# KAI_EFUSE_2_0_0.net
KiCad netlist of a schematic drawn in EAGLE
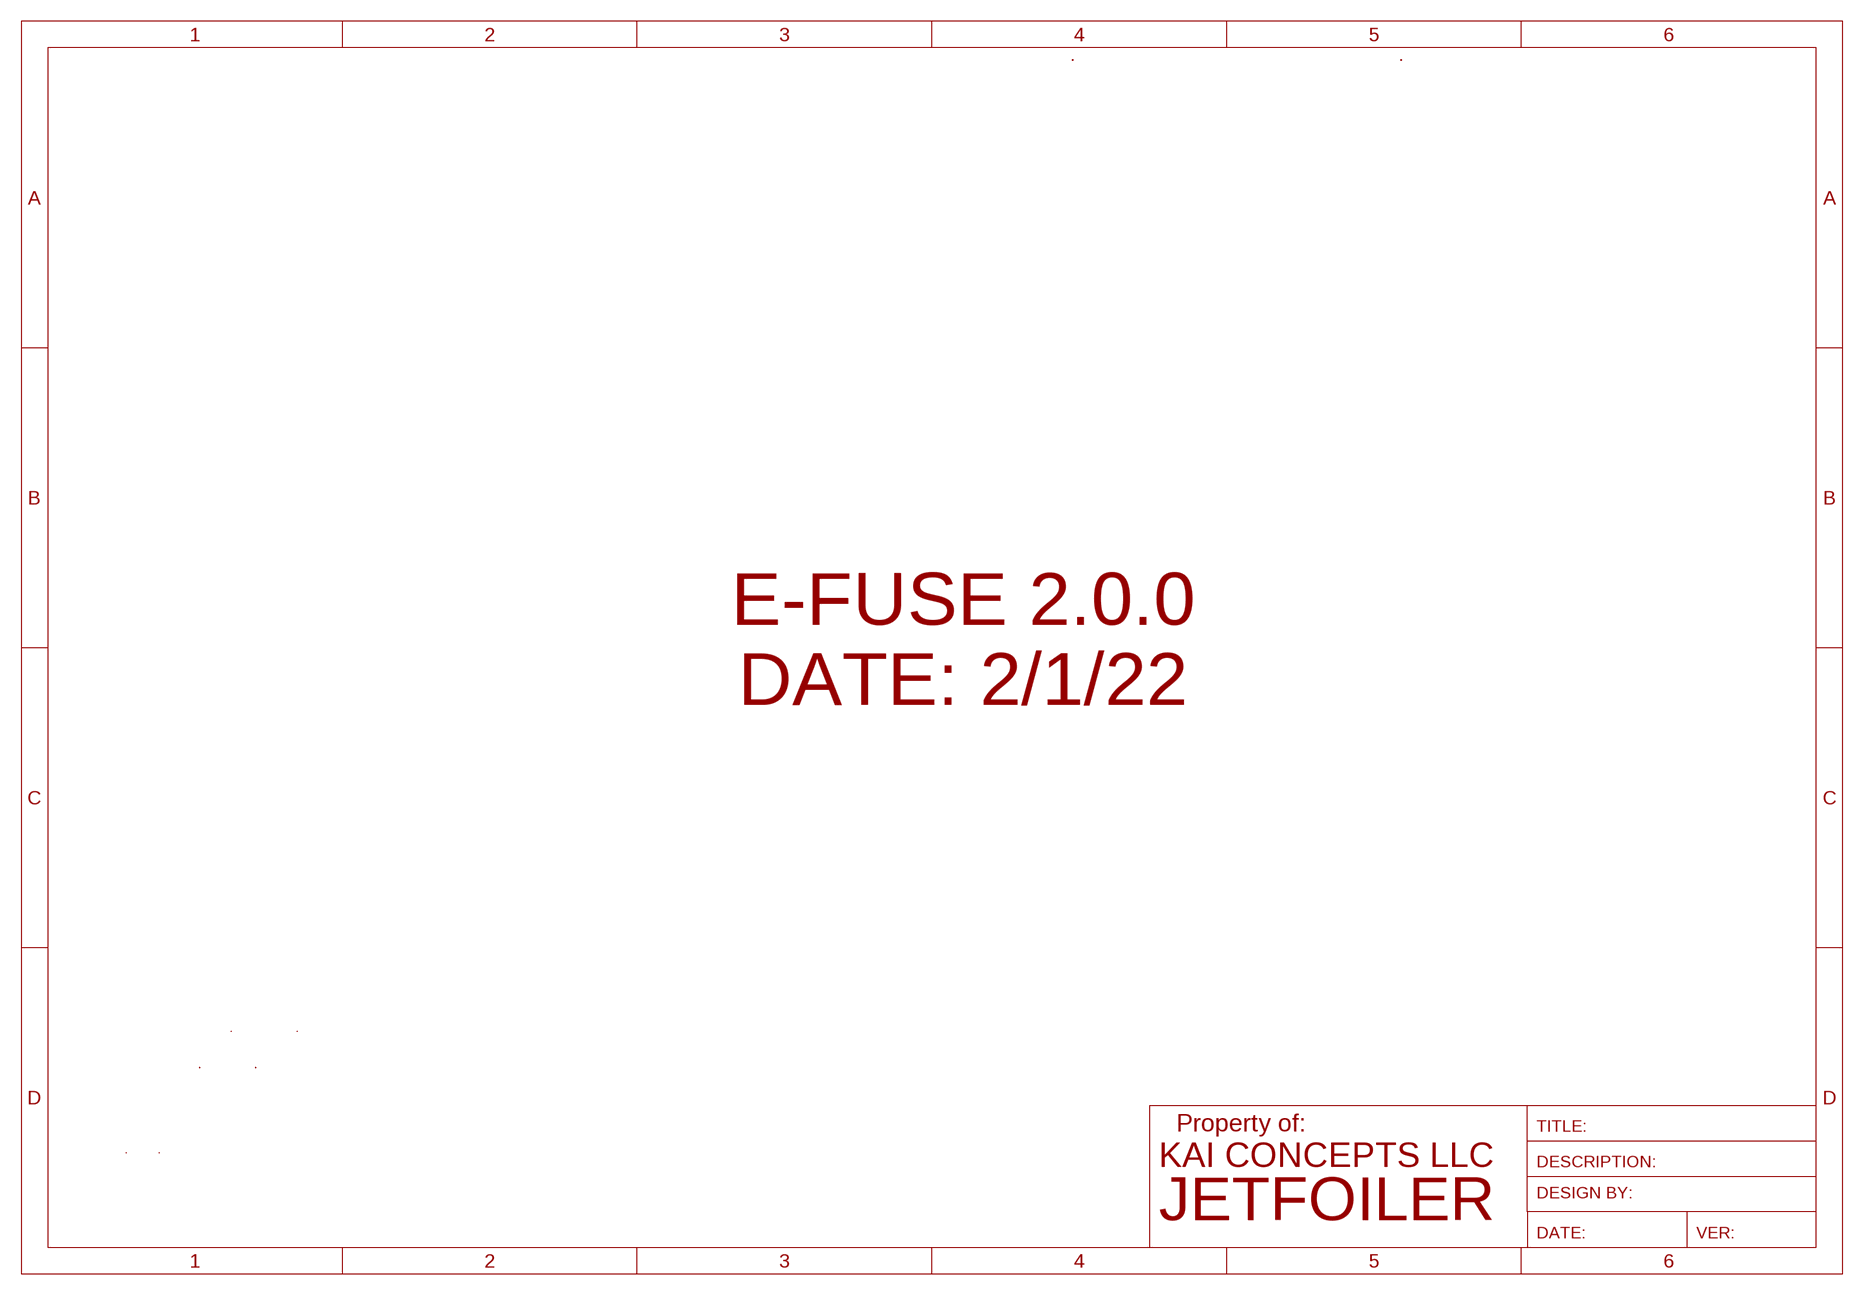
[diagram p0: schematic, sheet 1]
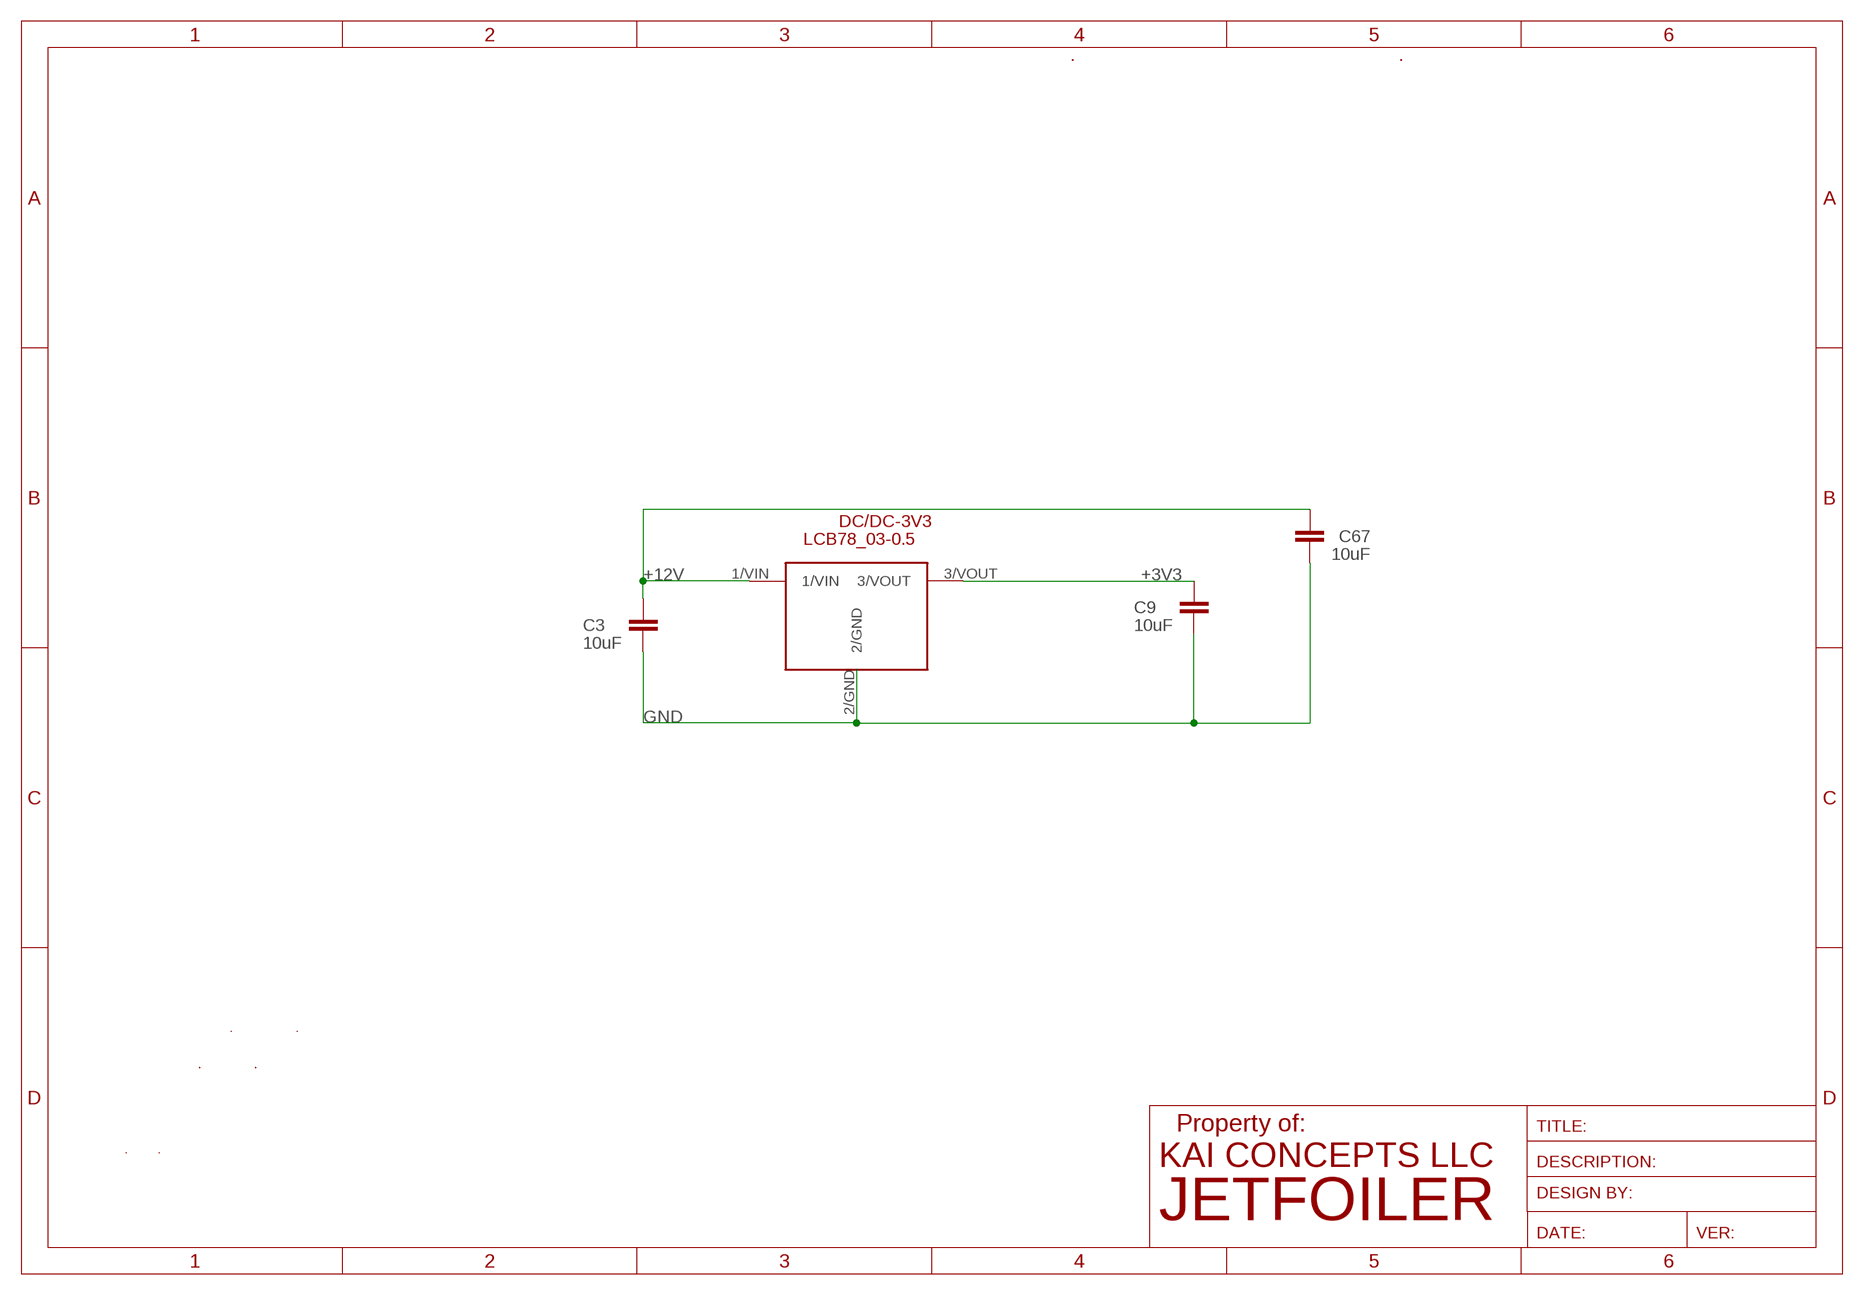
[diagram p1: schematic, sheet 2]
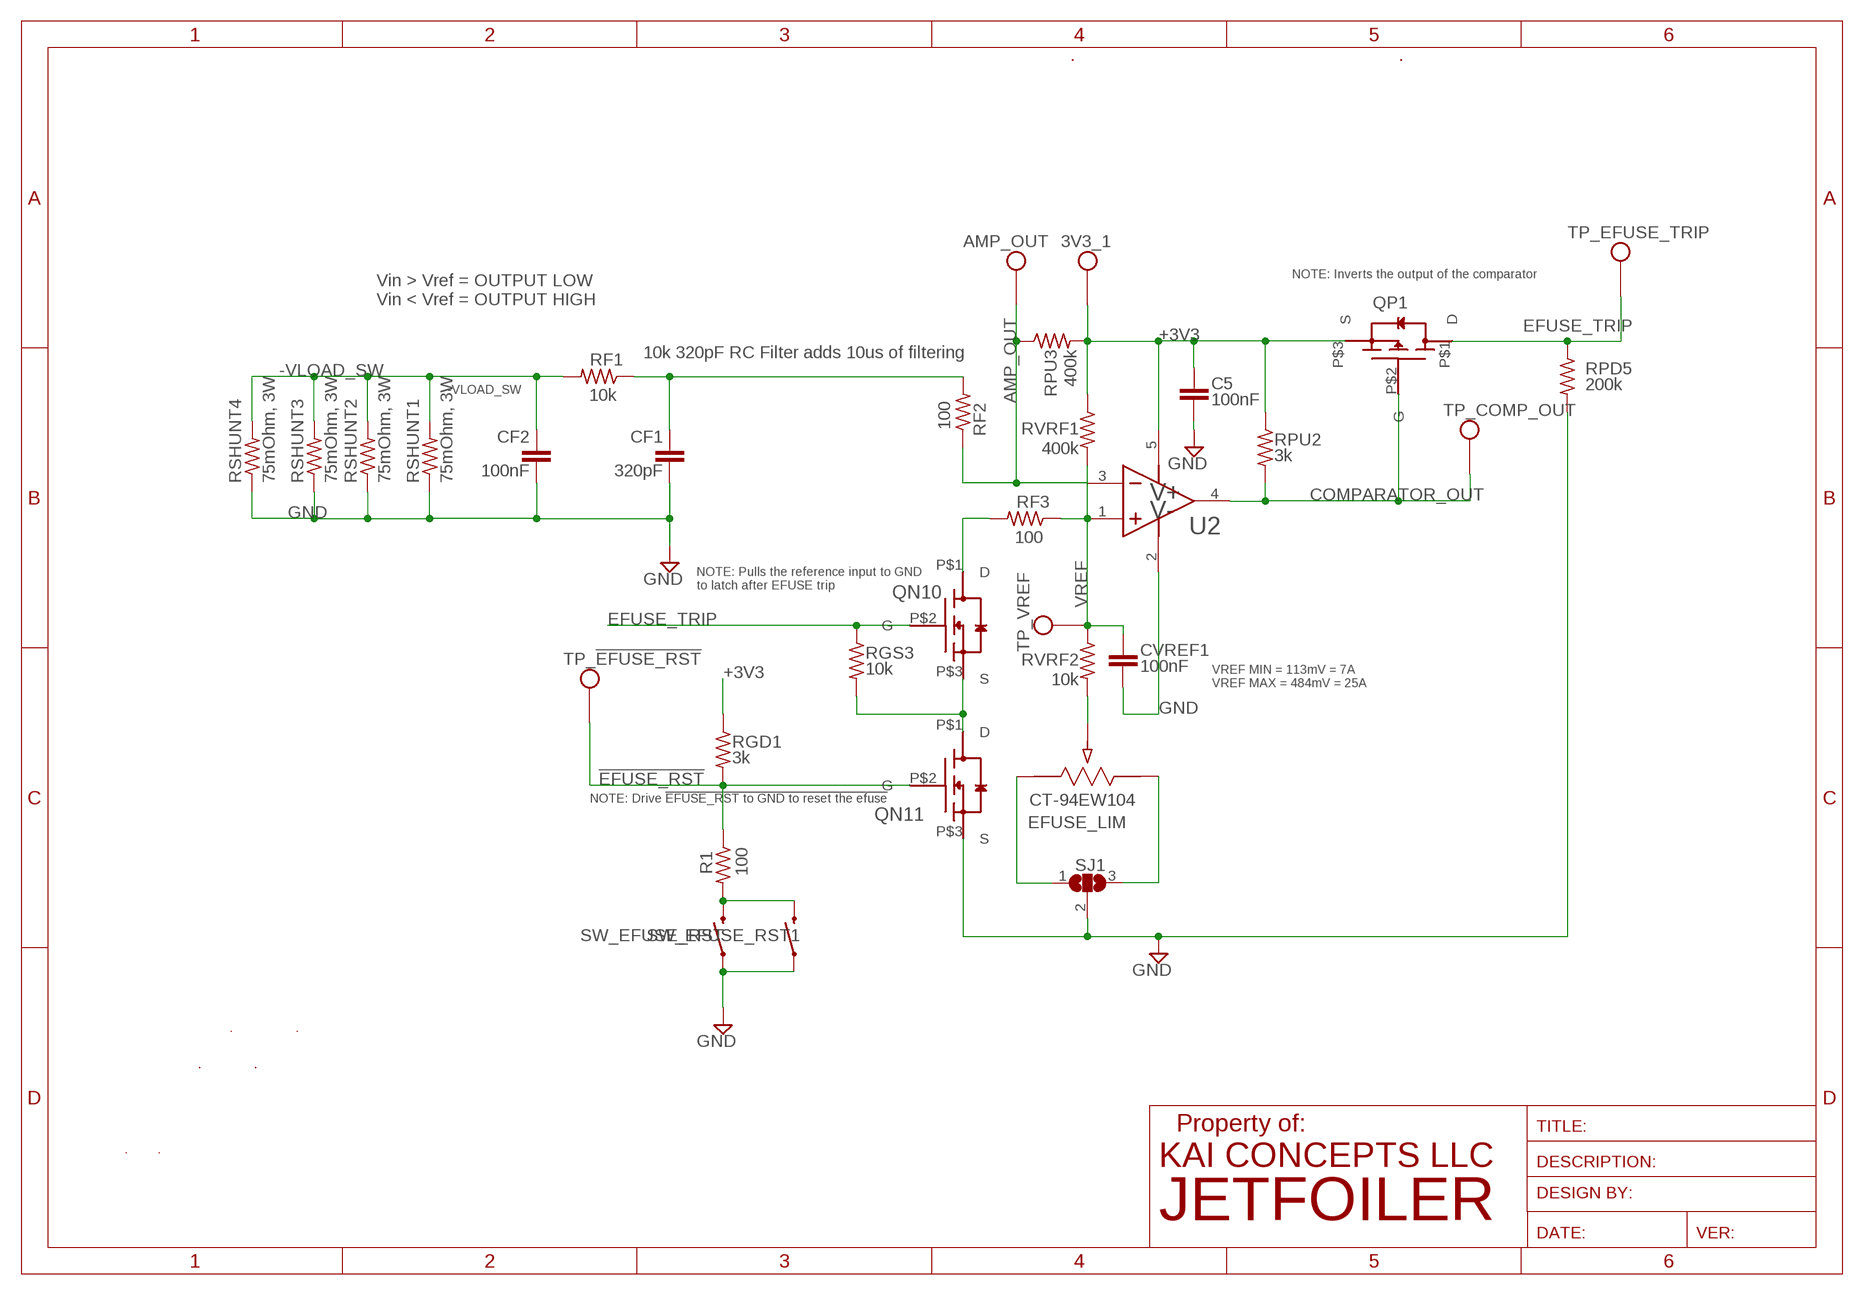
[diagram p2: schematic, sheet 3]
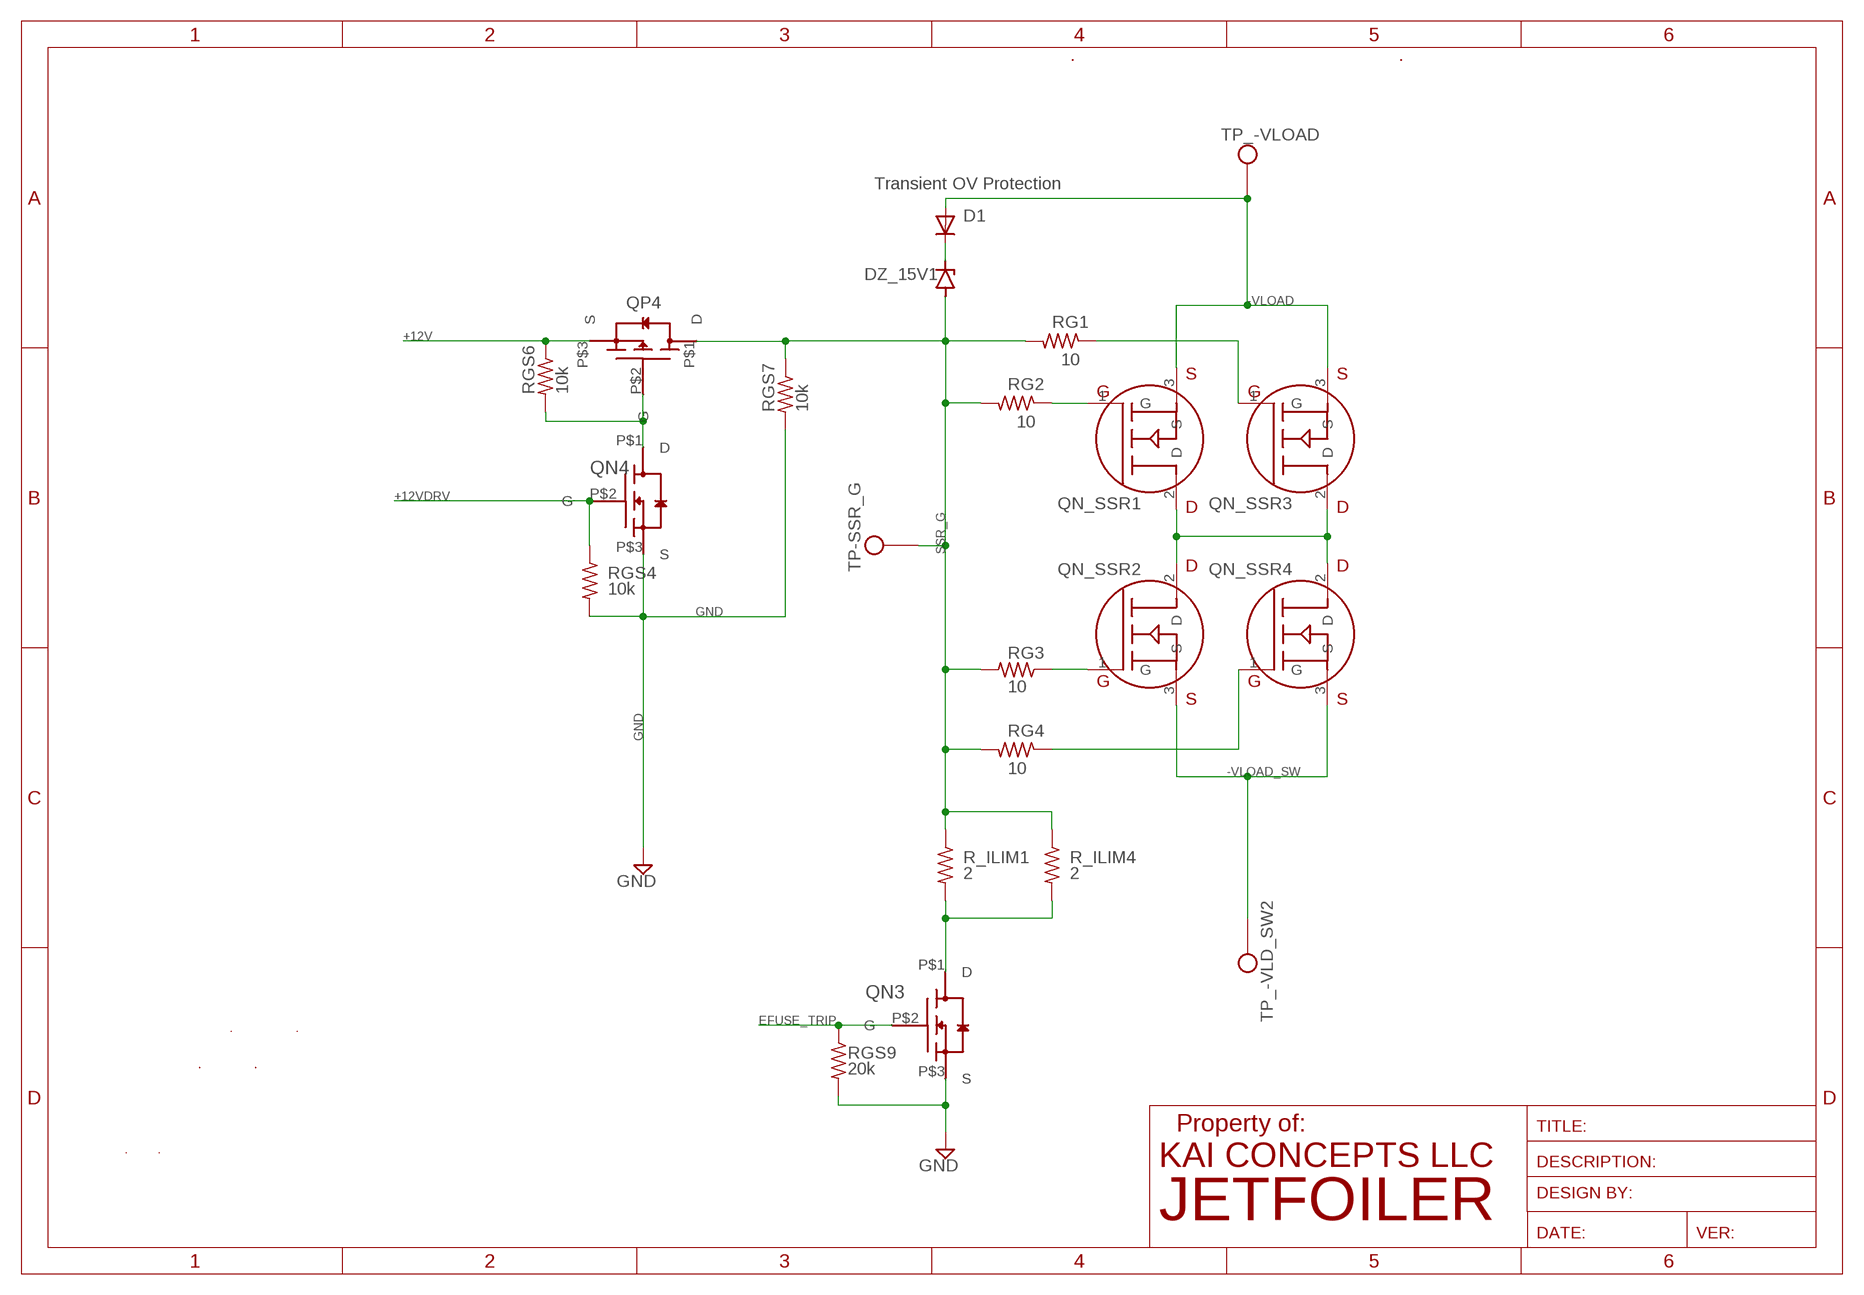
[diagram p3: schematic, sheet 4]
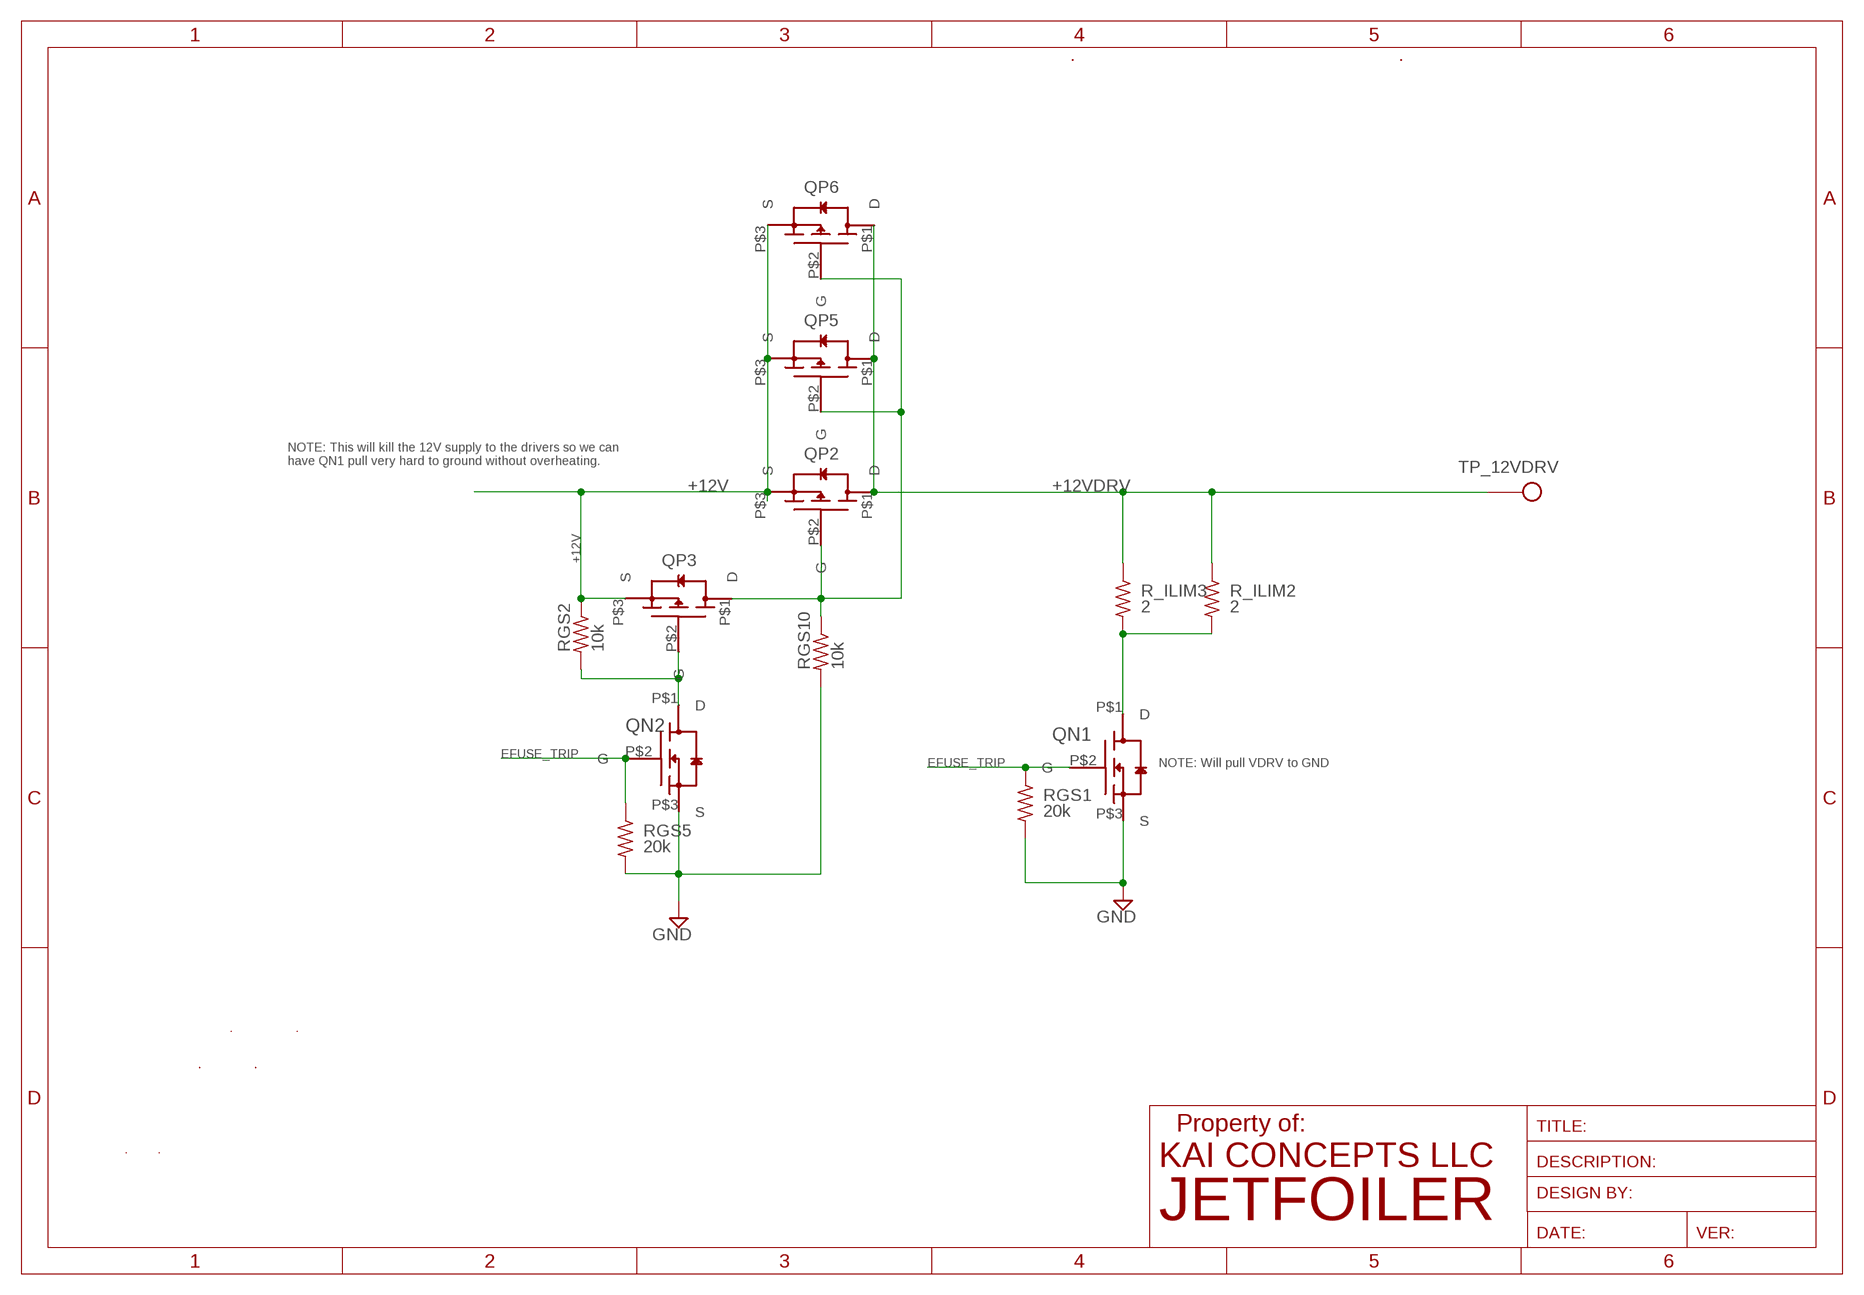
[diagram p4: schematic, sheet 5]
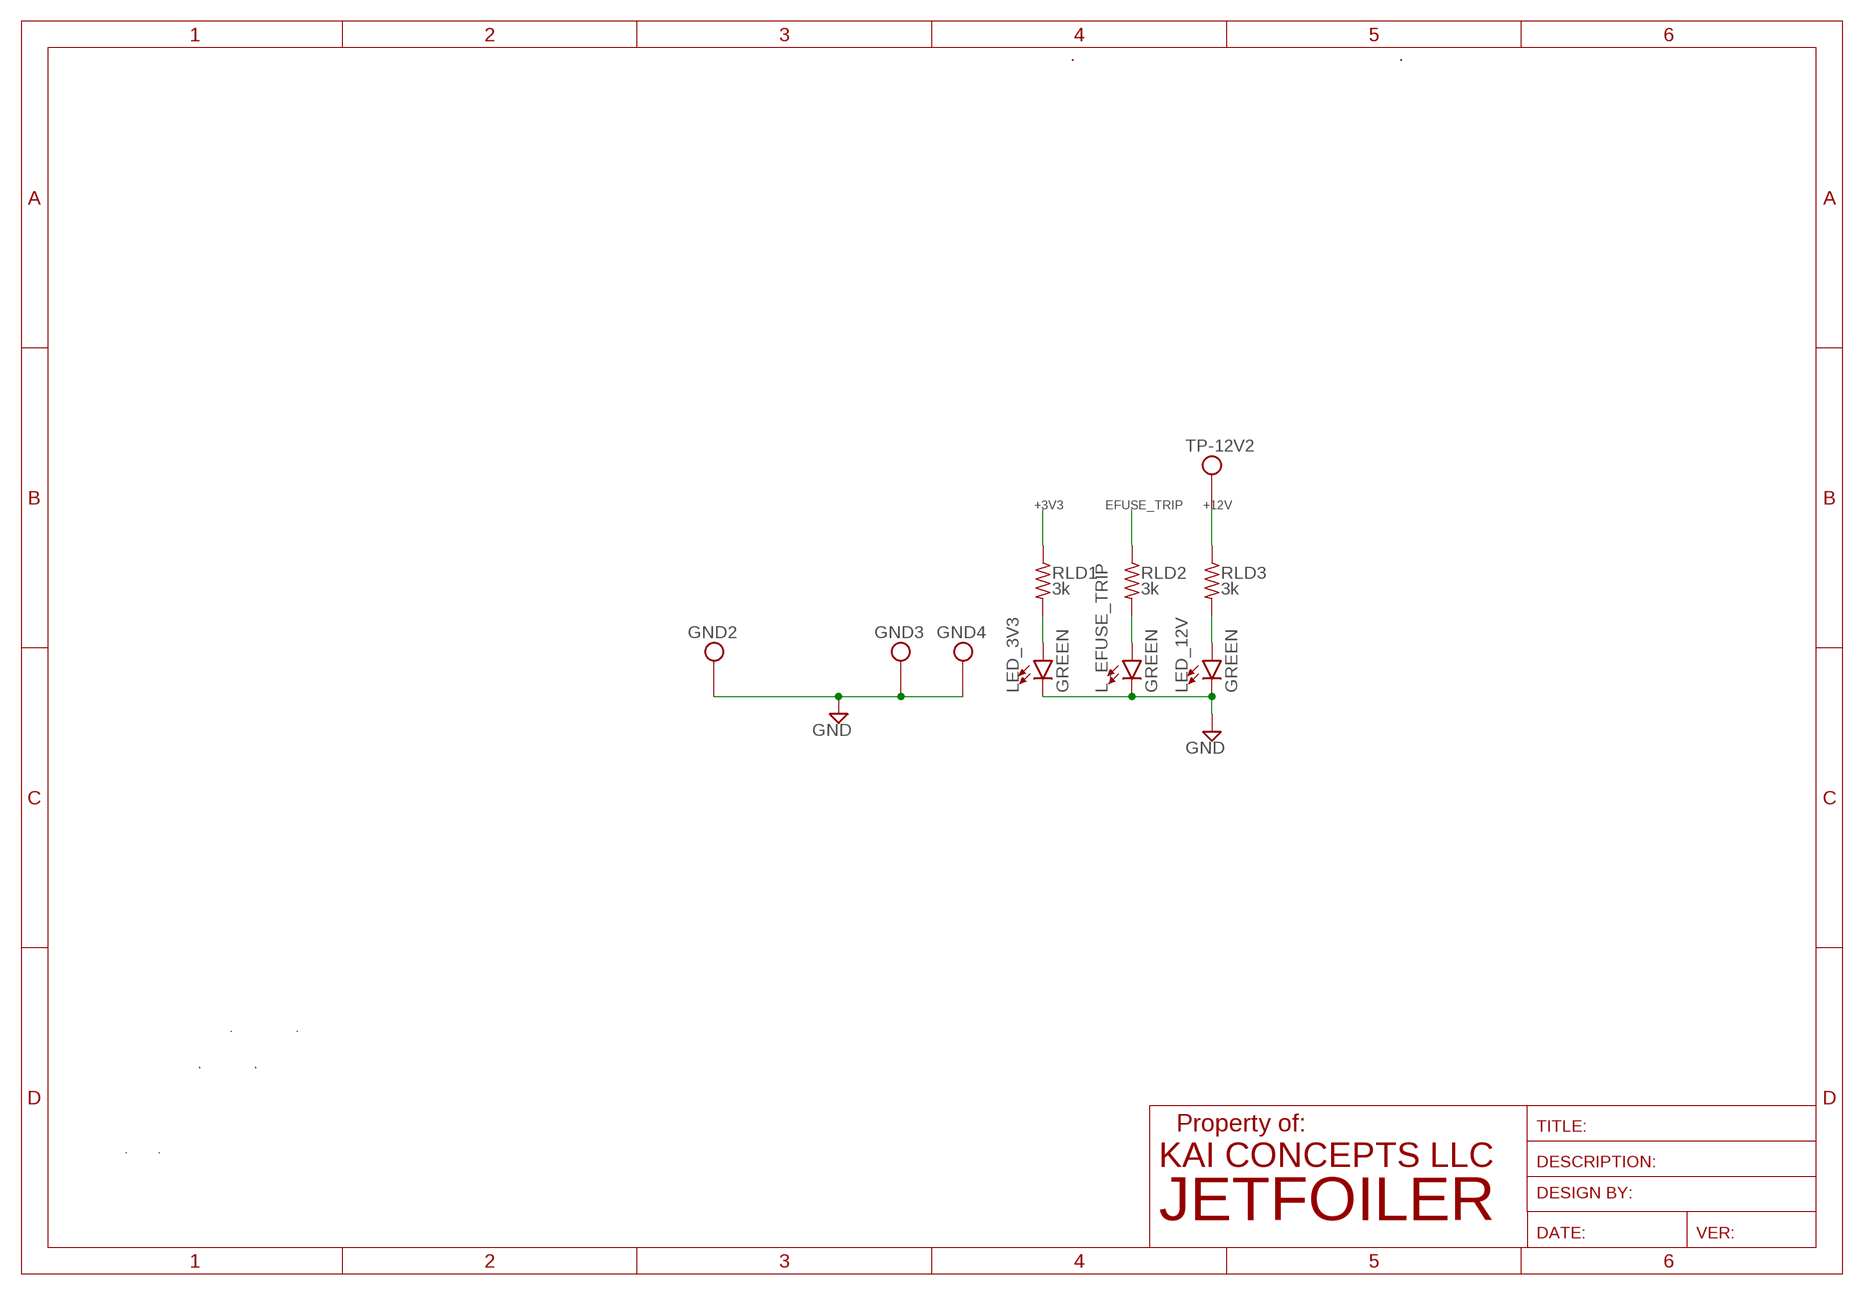
[diagram p5: schematic, sheet 6]
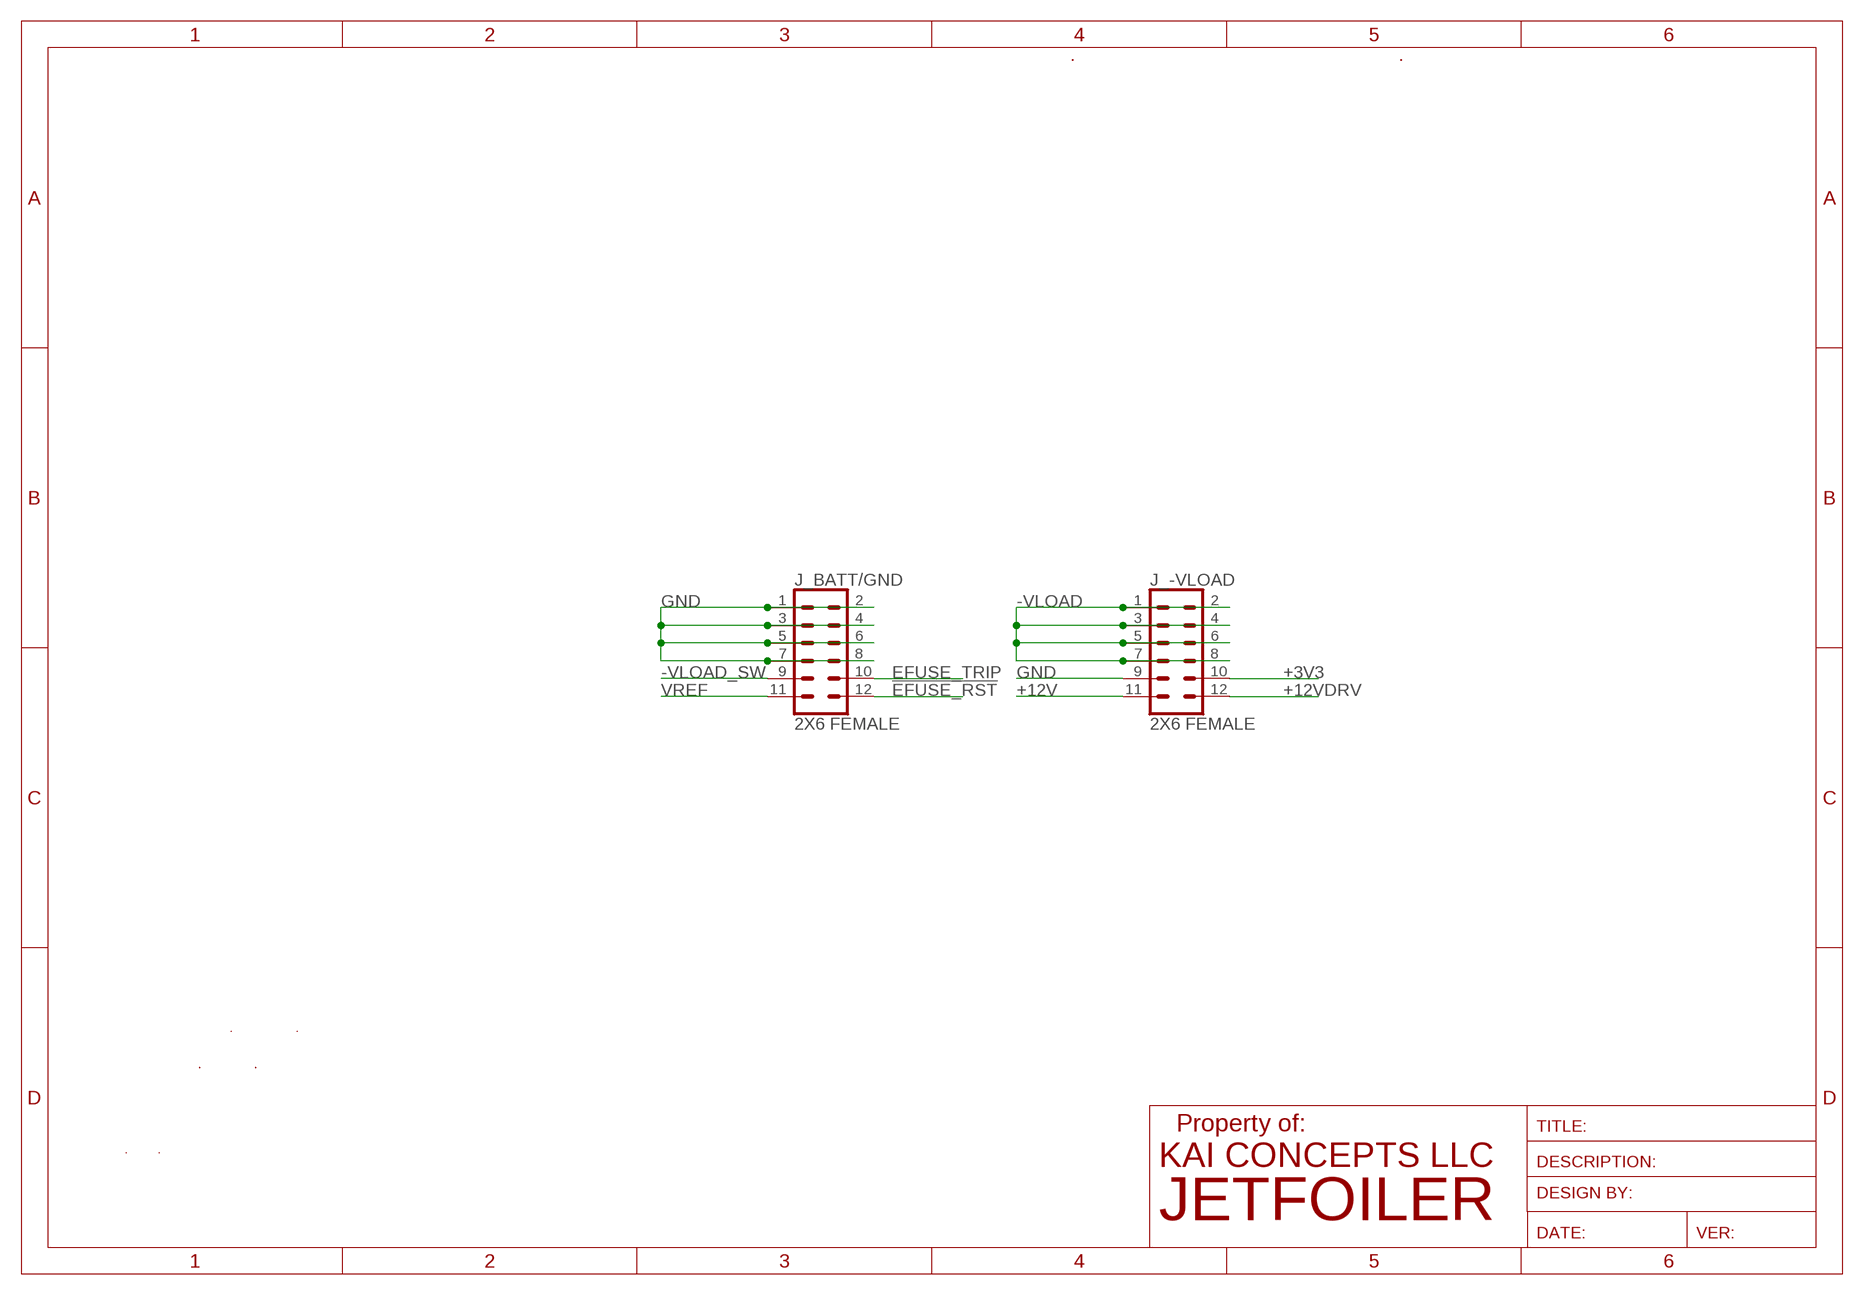
[diagram p6: schematic, sheet 7]
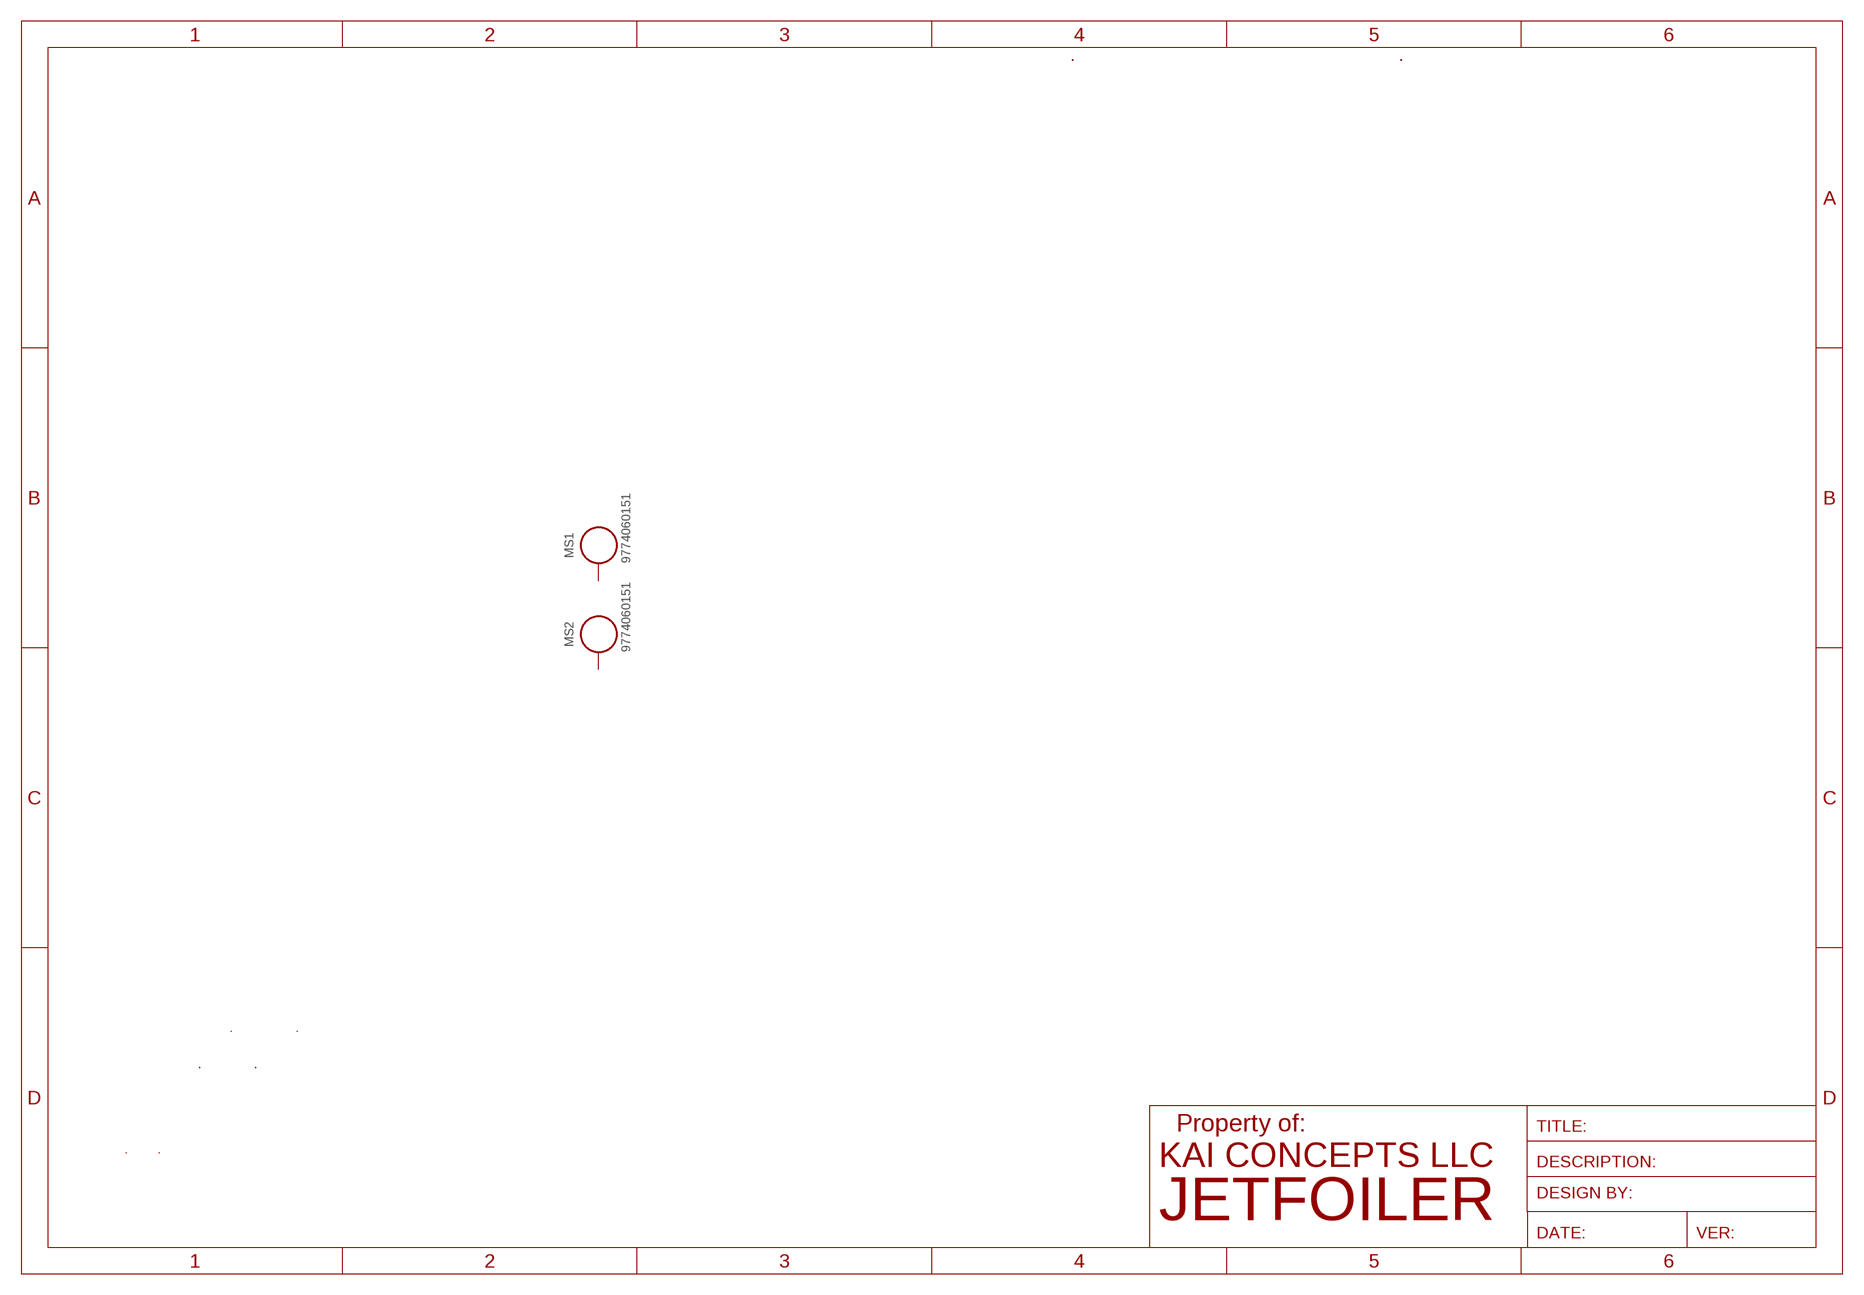
[diagram p7: schematic, sheet 8]

(export (version "E")
  (design (tool "Eeschema 10.0.6"))
  (components
    (comp (ref "QN1")
      (value "NFET-(SOT-23-3)(TO-236-3)(SC-59)")
      (footprint "eagle-import:SOT23,SC-59,TO-236-3")
      (fields (field (name "LCSC_PART") "C296286"))
      (libsource (lib "eagle-import") (part "NFET-(SOT-23-3)(TO-236-3)(SC-59)"))
    )
    (comp (ref "QN2")
      (value "NFET-(SOT-23-3)(TO-236-3)(SC-59)")
      (footprint "eagle-import:SOT23,SC-59,TO-236-3")
      (fields (field (name "LCSC_PART") "C296286"))
      (libsource (lib "eagle-import") (part "NFET-(SOT-23-3)(TO-236-3)(SC-59)"))
    )
    (comp (ref "QP2")
      (value "PFET-(SOT-23-3)(TO-236-3)(SC-59)")
      (footprint "eagle-import:SOT23,SC-59,TO-236-3")
      (fields (field (name "LCSC_PART") "C489594"))
      (libsource (lib "eagle-import") (part "PFET-(SOT-23-3)(TO-236-3)(SC-59)"))
    )
    (comp (ref "QP3")
      (value "PFET-(SOT-23-3)(TO-236-3)(SC-59)")
      (footprint "eagle-import:SOT23,SC-59,TO-236-3")
      (fields (field (name "LCSC_PART") "C489594"))
      (libsource (lib "eagle-import") (part "PFET-(SOT-23-3)(TO-236-3)(SC-59)"))
    )
    (comp (ref "QP5")
      (value "PFET-(SOT-23-3)(TO-236-3)(SC-59)")
      (footprint "eagle-import:SOT23,SC-59,TO-236-3")
      (fields (field (name "LCSC_PART") "C489594"))
      (libsource (lib "eagle-import") (part "PFET-(SOT-23-3)(TO-236-3)(SC-59)"))
    )
    (comp (ref "QP6")
      (value "PFET-(SOT-23-3)(TO-236-3)(SC-59)")
      (footprint "eagle-import:SOT23,SC-59,TO-236-3")
      (fields (field (name "LCSC_PART") "C489594"))
      (libsource (lib "eagle-import") (part "PFET-(SOT-23-3)(TO-236-3)(SC-59)"))
    )
    (comp (ref "RGS1")
      (value "20k")
      (footprint "eagle-import:R0603")
      (fields (field (name "LCSC_PART") "C118368"))
      (libsource (lib "eagle-import") (part "R-US_R0603"))
    )
    (comp (ref "RGS2")
      (value "10k")
      (footprint "eagle-import:R0603")
      (fields (field (name "LCSC_PART") "C116677"))
      (libsource (lib "eagle-import") (part "R-US_R0603"))
    )
    (comp (ref "RGS5")
      (value "20k")
      (footprint "eagle-import:R0603")
      (fields (field (name "LCSC_PART") "C118368"))
      (libsource (lib "eagle-import") (part "R-US_R0603"))
    )
    (comp (ref "RGS10")
      (value "10k")
      (footprint "eagle-import:R0603")
      (fields (field (name "LCSC_PART") "C116677"))
      (libsource (lib "eagle-import") (part "R-US_R0603"))
    )
    (comp (ref "R_ILIM2")
      (value "2")
      (footprint "eagle-import:R1206")
      (fields (field (name "LCSC_PART") "C102322"))
      (libsource (lib "eagle-import") (part "rcl_334_R-US_R1206"))
    )
    (comp (ref "R_ILIM3")
      (value "2")
      (footprint "eagle-import:R1206")
      (fields (field (name "LCSC_PART") "C102322"))
      (libsource (lib "eagle-import") (part "rcl_334_R-US_R1206"))
    )
    (comp (ref "TP_12VDRV")
      (value "THM_TESTPOINT_5000_SERIES")
      (footprint "eagle-import:THM-TESTPOINT")
      (libsource (lib "eagle-import") (part "THM_TESTPOINT_5000_SERIES"))
    )
    (comp (ref "3V3_1")
      (value "THM_TESTPOINT_5000_SERIES")
      (footprint "eagle-import:THM-TESTPOINT")
      (libsource (lib "eagle-import") (part "THM_TESTPOINT_5000_SERIES"))
    )
    (comp (ref "AMP_OUT")
      (value "THM_TESTPOINT_5000_SERIES")
      (footprint "eagle-import:THM-TESTPOINT")
      (libsource (lib "eagle-import") (part "THM_TESTPOINT_5000_SERIES"))
    )
    (comp (ref "C5")
      (value "100nF")
      (footprint "eagle-import:C0603")
      (fields (field (name "LCSC_PART") "C14663"))
      (libsource (lib "eagle-import") (part "C-EUC0603"))
    )
    (comp (ref "CF1")
      (value "320pF")
      (footprint "eagle-import:C0603")
      (fields (field (name "LCSC_PART") "C14663"))
      (libsource (lib "eagle-import") (part "rcl_334_C-EUC0603"))
    )
    (comp (ref "CF2")
      (value "100nF")
      (footprint "eagle-import:C0603")
      (fields (field (name "LCSC_PART") "C14663"))
      (libsource (lib "eagle-import") (part "rcl_334_C-EUC0603"))
    )
    (comp (ref "CVREF1")
      (value "100nF")
      (footprint "eagle-import:C0603")
      (fields (field (name "LCSC_PART") "C14663"))
      (libsource (lib "eagle-import") (part "C-EUC0603"))
    )
    (comp (ref "EFUSE_LIM")
      (value "CT-94EW104")
      (footprint "eagle-import:POT_CT-94EW_NDC")
      (fields
        (field (name "LCSC_PART") "DNP")
        (field (name "COPYRIGHT") "Copyright (C) 2021 Ultra Librarian. All rights reserved.")
      )
      (libsource (lib "eagle-import") (part "CT-94EW104"))
    )
    (comp (ref "QN10")
      (value "NFET-(SOT-23-3)(TO-236-3)(SC-59)")
      (footprint "eagle-import:SOT23,SC-59,TO-236-3")
      (fields (field (name "LCSC_PART") "C296286"))
      (libsource (lib "eagle-import") (part "NFET-(SOT-23-3)(TO-236-3)(SC-59)"))
    )
    (comp (ref "QN11")
      (value "NFET-(SOT-23-3)(TO-236-3)(SC-59)")
      (footprint "eagle-import:SOT23,SC-59,TO-236-3")
      (fields (field (name "LCSC_PART") "C296286"))
      (libsource (lib "eagle-import") (part "NFET-(SOT-23-3)(TO-236-3)(SC-59)"))
    )
    (comp (ref "QP1")
      (value "PFET-(SOT-23-3)(TO-236-3)(SC-59)")
      (footprint "eagle-import:SOT23,SC-59,TO-236-3")
      (fields (field (name "LCSC_PART") "C489594"))
      (libsource (lib "eagle-import") (part "PFET-(SOT-23-3)(TO-236-3)(SC-59)"))
    )
    (comp (ref "R1")
      (value "100")
      (footprint "eagle-import:R0603")
      (fields (field (name "LCSC_PART") "C103197"))
      (libsource (lib "eagle-import") (part "R-US_R0603"))
    )
    (comp (ref "RF1")
      (value "10k")
      (footprint "eagle-import:R0603")
      (fields (field (name "LCSC_PART") "C491175"))
      (libsource (lib "eagle-import") (part "R-US_R0603"))
    )
    (comp (ref "RF2")
      (value "100")
      (footprint "eagle-import:R0603")
      (fields (field (name "LCSC_PART") "C103197"))
      (libsource (lib "eagle-import") (part "R-US_R0603"))
    )
    (comp (ref "RF3")
      (value "100")
      (footprint "eagle-import:R0603")
      (fields (field (name "LCSC_PART") "C103197"))
      (libsource (lib "eagle-import") (part "R-US_R0603"))
    )
    (comp (ref "RGD1")
      (value "3k")
      (footprint "eagle-import:R0603")
      (fields (field (name "LCSC_PART") "C126358"))
      (libsource (lib "eagle-import") (part "R-US_R0603"))
    )
    (comp (ref "RGS3")
      (value "10k")
      (footprint "eagle-import:R0603")
      (fields (field (name "LCSC_PART") "C116677"))
      (libsource (lib "eagle-import") (part "R-US_R0603"))
    )
    (comp (ref "RPD5")
      (value "200k")
      (footprint "eagle-import:R0603")
      (fields (field (name "LCSC_PART") "C95331"))
      (libsource (lib "eagle-import") (part "R-US_R0603"))
    )
    (comp (ref "RPU2")
      (value "3k")
      (footprint "eagle-import:R0603")
      (fields (field (name "LCSC_PART") "C126358"))
      (libsource (lib "eagle-import") (part "R-US_R0603"))
    )
    (comp (ref "RPU3")
      (value "400k")
      (footprint "eagle-import:R0603")
      (fields (field (name "LCSC_PART") "C209133"))
      (libsource (lib "eagle-import") (part "R-US_R0603"))
    )
    (comp (ref "RSHUNT1")
      (value "75mOhm, 3W")
      (footprint "eagle-import:R2512")
      (fields (field (name "LCSC_PART") "C459689"))
      (libsource (lib "eagle-import") (part "rcl_334_R-US_R2512"))
    )
    (comp (ref "RSHUNT2")
      (value "75mOhm, 3W")
      (footprint "eagle-import:R2512")
      (fields (field (name "LCSC_PART") "C459689"))
      (libsource (lib "eagle-import") (part "rcl_334_R-US_R2512"))
    )
    (comp (ref "RSHUNT3")
      (value "75mOhm, 3W")
      (footprint "eagle-import:R2512")
      (fields (field (name "LCSC_PART") "C459689"))
      (libsource (lib "eagle-import") (part "rcl_334_R-US_R2512"))
    )
    (comp (ref "RSHUNT4")
      (value "75mOhm, 3W")
      (footprint "eagle-import:R2512")
      (fields (field (name "LCSC_PART") "C459689"))
      (libsource (lib "eagle-import") (part "rcl_334_R-US_R2512"))
    )
    (comp (ref "RVRF1")
      (value "400k")
      (footprint "eagle-import:R0603")
      (fields (field (name "LCSC_PART") "C209133"))
      (libsource (lib "eagle-import") (part "R-US_R0603"))
    )
    (comp (ref "RVRF2")
      (value "10k")
      (footprint "eagle-import:R0603")
      (fields (field (name "LCSC_PART") "C116677"))
      (libsource (lib "eagle-import") (part "R-US_R0603"))
    )
    (comp (ref "SJ1")
      (value "SJ2W")
      (footprint "eagle-import:SJ_2")
      (fields (field (name "LCSC_PART") "DNP"))
      (libsource (lib "eagle-import") (part "SJ2W"))
    )
    (comp (ref "SW_EFUSE_RST")
      (value "MOMENTARY-SWITCH-SPST-SMD-6.0X3.5MM")
      (footprint "eagle-import:TACTILE_SWITCH_SMD_6.0X3.5MM")
      (fields (field (name "LCSC_PART") "C520860"))
      (libsource (lib "eagle-import") (part "MOMENTARY-SWITCH-SPST-SMD-6.0X3.5MM"))
    )
    (comp (ref "SW_EFUSE_RST1")
      (value "MOMENTARY-SWITCH-SPST-SMD-6.0X3.5MM")
      (footprint "eagle-import:TACTILE_SWITCH_SMD_6.0X3.5MM")
      (fields (field (name "LCSC_PART") "C520860"))
      (libsource (lib "eagle-import") (part "MOMENTARY-SWITCH-SPST-SMD-6.0X3.5MM"))
    )
    (comp (ref "TP_!EFUSE_RST")
      (value "THM_TESTPOINT_5000_SERIES")
      (footprint "eagle-import:THM-TESTPOINT")
      (libsource (lib "eagle-import") (part "THM_TESTPOINT_5000_SERIES"))
    )
    (comp (ref "TP_COMP_OUT")
      (value "THM_TESTPOINT_5000_SERIES")
      (footprint "eagle-import:THM-TESTPOINT")
      (libsource (lib "eagle-import") (part "THM_TESTPOINT_5000_SERIES"))
    )
    (comp (ref "TP_EFUSE_TRIP")
      (value "THM_TESTPOINT_5000_SERIES")
      (footprint "eagle-import:THM-TESTPOINT")
      (libsource (lib "eagle-import") (part "THM_TESTPOINT_5000_SERIES"))
    )
    (comp (ref "TP_VREF")
      (value "THM_TESTPOINT_5000_SERIES")
      (footprint "eagle-import:THM-TESTPOINT")
      (libsource (lib "eagle-import") (part "THM_TESTPOINT_5000_SERIES"))
    )
    (comp (ref "U2")
      (value "LMV331M5X")
      (footprint "eagle-import:MF05A")
      (fields
        (field (name "LCSC_PART") "C253067")
        (field (name "COPYRIGHT") "Copyright (C) 2021 Ultra Librarian. All rights reserved.")
      )
      (libsource (lib "eagle-import") (part "LMV331M5X"))
    )
    (comp (ref "C3")
      (value "10uF")
      (footprint "eagle-import:C1206")
      (fields (field (name "LCSC_PART") "C13585"))
      (libsource (lib "eagle-import") (part "rcl_334_C-EUC1206"))
    )
    (comp (ref "C9")
      (value "10uF")
      (footprint "eagle-import:C1206")
      (fields (field (name "LCSC_PART") "C13585"))
      (libsource (lib "eagle-import") (part "rcl_334_C-EUC1206"))
    )
    (comp (ref "C67")
      (value "10uF")
      (footprint "eagle-import:C1206")
      (fields (field (name "LCSC_PART") "C13585"))
      (libsource (lib "eagle-import") (part "rcl_334_C-EUC1206"))
    )
    (comp (ref "DC/DC-3V3")
      (value "LCB78_03-0.5")
      (footprint "eagle-import:3-SIP")
      (fields (field (name "LCSC_PART") "DNP"))
      (libsource (lib "eagle-import") (part "3-SIP"))
    )
    (comp (ref "MS1")
      (value "9774060151")
      (footprint "eagle-import:WA-SMSI_9774060151")
      (fields (field (name "LCSC_PART") "DNP"))
      (libsource (lib "eagle-import") (part "WA-SMSI_9774XXX151_9774060151"))
    )
    (comp (ref "MS2")
      (value "9774060151")
      (footprint "eagle-import:WA-SMSI_9774060151")
      (fields (field (name "LCSC_PART") "DNP"))
      (libsource (lib "eagle-import") (part "WA-SMSI_9774XXX151_9774060151"))
    )
    (comp (ref "J_-VLOAD")
      (value "2X6 FEMALE")
      (footprint "eagle-import:2X6")
      (fields (field (name "LCSC_PART") "DNP"))
      (libsource (lib "eagle-import") (part "CONN_06X2PTH_FEMALE"))
    )
    (comp (ref "J_BATT/GND")
      (value "2X6 FEMALE")
      (footprint "eagle-import:2X6")
      (fields (field (name "LCSC_PART") "DNP"))
      (libsource (lib "eagle-import") (part "CONN_06X2PTH_FEMALE"))
    )
    (comp (ref "GND2")
      (value "THM_TESTPOINT_5000_SERIES")
      (footprint "eagle-import:THM-TESTPOINT")
      (libsource (lib "eagle-import") (part "THM_TESTPOINT_5000_SERIES"))
    )
    (comp (ref "GND3")
      (value "THM_TESTPOINT_5000_SERIES")
      (footprint "eagle-import:THM-TESTPOINT")
      (libsource (lib "eagle-import") (part "THM_TESTPOINT_5000_SERIES"))
    )
    (comp (ref "GND4")
      (value "THM_TESTPOINT_5000_SERIES")
      (footprint "eagle-import:THM-TESTPOINT")
      (libsource (lib "eagle-import") (part "THM_TESTPOINT_5000_SERIES"))
    )
    (comp (ref "LED_3V3")
      (value "GREEN")
      (footprint "eagle-import:LED-1206")
      (fields (field (name "LCSC_PART") "C434439"))
      (libsource (lib "eagle-import") (part "LED-GREEN1206"))
    )
    (comp (ref "LED_12V")
      (value "GREEN")
      (footprint "eagle-import:LED-1206")
      (fields (field (name "LCSC_PART") "C434439"))
      (libsource (lib "eagle-import") (part "LED-GREEN1206"))
    )
    (comp (ref "L_EFUSE_TRIP")
      (value "GREEN")
      (footprint "eagle-import:LED-1206")
      (fields (field (name "LCSC_PART") "C434439"))
      (libsource (lib "eagle-import") (part "LED-GREEN1206"))
    )
    (comp (ref "RLD1")
      (value "3k")
      (footprint "eagle-import:R0603")
      (fields (field (name "LCSC_PART") "C126358"))
      (libsource (lib "eagle-import") (part "R-US_R0603"))
    )
    (comp (ref "RLD2")
      (value "3k")
      (footprint "eagle-import:R0603")
      (fields (field (name "LCSC_PART") "C126358"))
      (libsource (lib "eagle-import") (part "R-US_R0603"))
    )
    (comp (ref "RLD3")
      (value "3k")
      (footprint "eagle-import:R0603")
      (fields (field (name "LCSC_PART") "C126358"))
      (libsource (lib "eagle-import") (part "R-US_R0603"))
    )
    (comp (ref "TP-12V2")
      (value "THM_TESTPOINT_5000_SERIES")
      (footprint "eagle-import:THM-TESTPOINT")
      (libsource (lib "eagle-import") (part "THM_TESTPOINT_5000_SERIES"))
    )
    (comp (ref "D1")
      (value "DIODESMA")
      (footprint "eagle-import:SMADIODE")
      (fields (field (name "LCSC_PART") "C110531"))
      (libsource (lib "eagle-import") (part "DIODESMA"))
    )
    (comp (ref "DZ_15V1")
      (value "NZH15B,115")
      (footprint "eagle-import:SODFL3718X115")
      (fields
        (field (name "MANUFACTURER") "ON Semiconductor ")
        (field (name "MPN") "MMSZ5240BT1G")
        (field (name "LCSC_PART") "C173428")
      )
      (libsource (lib "eagle-import") (part "ZENER_DO-219-AB(SOD123F)MMSZ5240BT"))
    )
    (comp (ref "QN3")
      (value "NFET-(SOT-23-3)(TO-236-3)(SC-59)")
      (footprint "eagle-import:SOT23,SC-59,TO-236-3")
      (fields (field (name "LCSC_PART") "C296286"))
      (libsource (lib "eagle-import") (part "NFET-(SOT-23-3)(TO-236-3)(SC-59)"))
    )
    (comp (ref "QN4")
      (value "NFET-(SOT-23-3)(TO-236-3)(SC-59)")
      (footprint "eagle-import:SOT23,SC-59,TO-236-3")
      (fields (field (name "LCSC_PART") "C296286"))
      (libsource (lib "eagle-import") (part "NFET-(SOT-23-3)(TO-236-3)(SC-59)"))
    )
    (comp (ref "QN_SSR1")
      (value "IPB60R060P7ATMA1")
      (footprint "eagle-import:D2PACK")
      (fields (field (name "LCSC_PART") "DNP"))
      (libsource (lib "eagle-import") (part "IPB60R060P7ATMA1"))
    )
    (comp (ref "QN_SSR2")
      (value "IPB60R060P7ATMA1")
      (footprint "eagle-import:D2PACK")
      (fields (field (name "LCSC_PART") "DNP"))
      (libsource (lib "eagle-import") (part "IPB60R060P7ATMA1"))
    )
    (comp (ref "QN_SSR3")
      (value "IPB60R060P7ATMA1")
      (footprint "eagle-import:D2PACK")
      (fields (field (name "LCSC_PART") "DNP"))
      (libsource (lib "eagle-import") (part "IPB60R060P7ATMA1"))
    )
    (comp (ref "QN_SSR4")
      (value "IPB60R060P7ATMA1")
      (footprint "eagle-import:D2PACK")
      (fields (field (name "LCSC_PART") "DNP"))
      (libsource (lib "eagle-import") (part "IPB60R060P7ATMA1"))
    )
    (comp (ref "QP4")
      (value "PFET-(SOT-23-3)(TO-236-3)(SC-59)")
      (footprint "eagle-import:SOT23,SC-59,TO-236-3")
      (fields (field (name "LCSC_PART") "C489594"))
      (libsource (lib "eagle-import") (part "PFET-(SOT-23-3)(TO-236-3)(SC-59)"))
    )
    (comp (ref "RG1")
      (value "10")
      (footprint "eagle-import:R1206")
      (fields (field (name "LCSC_PART") "C326706"))
      (libsource (lib "eagle-import") (part "rcl_334_R-US_R1206"))
    )
    (comp (ref "RG2")
      (value "10")
      (footprint "eagle-import:R1206")
      (fields (field (name "LCSC_PART") "C326706"))
      (libsource (lib "eagle-import") (part "rcl_334_R-US_R1206"))
    )
    (comp (ref "RG3")
      (value "10")
      (footprint "eagle-import:R1206")
      (fields (field (name "LCSC_PART") "C326706"))
      (libsource (lib "eagle-import") (part "rcl_334_R-US_R1206"))
    )
    (comp (ref "RG4")
      (value "10")
      (footprint "eagle-import:R1206")
      (fields (field (name "LCSC_PART") "C326706"))
      (libsource (lib "eagle-import") (part "rcl_334_R-US_R1206"))
    )
    (comp (ref "RGS4")
      (value "10k")
      (footprint "eagle-import:R0603")
      (fields (field (name "LCSC_PART") "C116677"))
      (libsource (lib "eagle-import") (part "R-US_R0603"))
    )
    (comp (ref "RGS6")
      (value "10k")
      (footprint "eagle-import:R0603")
      (fields (field (name "LCSC_PART") "C116677"))
      (libsource (lib "eagle-import") (part "R-US_R0603"))
    )
    (comp (ref "RGS7")
      (value "10k")
      (footprint "eagle-import:R0603")
      (fields (field (name "LCSC_PART") "C116677"))
      (libsource (lib "eagle-import") (part "R-US_R0603"))
    )
    (comp (ref "RGS9")
      (value "20k")
      (footprint "eagle-import:R0603")
      (fields (field (name "LCSC_PART") "C118368"))
      (libsource (lib "eagle-import") (part "R-US_R0603"))
    )
    (comp (ref "R_ILIM1")
      (value "2")
      (footprint "eagle-import:R1206")
      (fields (field (name "LCSC_PART") "C102322"))
      (libsource (lib "eagle-import") (part "rcl_334_R-US_R1206"))
    )
    (comp (ref "R_ILIM4")
      (value "2")
      (footprint "eagle-import:R1206")
      (fields (field (name "LCSC_PART") "C102322"))
      (libsource (lib "eagle-import") (part "rcl_334_R-US_R1206"))
    )
    (comp (ref "TP-SSR_G")
      (value "THM_TESTPOINT_5000_SERIES")
      (footprint "eagle-import:THM-TESTPOINT")
      (libsource (lib "eagle-import") (part "THM_TESTPOINT_5000_SERIES"))
    )
    (comp (ref "TP_-VLD_SW2")
      (value "THM_TESTPOINT_5000_SERIES")
      (footprint "eagle-import:THM-TESTPOINT")
      (libsource (lib "eagle-import") (part "THM_TESTPOINT_5000_SERIES"))
    )
    (comp (ref "TP_-VLOAD")
      (value "THM_TESTPOINT_5000_SERIES")
      (footprint "eagle-import:THM-TESTPOINT")
      (libsource (lib "eagle-import") (part "THM_TESTPOINT_5000_SERIES"))
    )
  )
  (nets
    (net (code "1") (name "+3V3") (class "Default")
      (node (ref "3V3_1") (pin "P1") (pinfunction "P$1_P1") (pintype "bidirectional"))
      (node (ref "C5") (pin "1") (pinfunction "1_1") (pintype "passive"))
      (node (ref "C9") (pin "2") (pinfunction "2_2") (pintype "passive"))
      (node (ref "DC/DC-3V3") (pin "3/VOUT") (pinfunction "3/VOUT_3/VOUT") (pintype "bidirectional"))
      (node (ref "J_-VLOAD") (pin "10") (pinfunction "10_10") (pintype "passive"))
      (node (ref "QP1") (pin "P$3") (pinfunction "S_P$3") (pintype "bidirectional"))
      (node (ref "RGD1") (pin "1") (pinfunction "1_1") (pintype "passive"))
      (node (ref "RLD1") (pin "1") (pinfunction "1_1") (pintype "passive"))
      (node (ref "RPU2") (pin "1") (pinfunction "1_1") (pintype "passive"))
      (node (ref "RPU3") (pin "2") (pinfunction "2_2") (pintype "passive"))
      (node (ref "RVRF1") (pin "1") (pinfunction "1_1") (pintype "passive"))
      (node (ref "U2") (pin "5") (pinfunction "V+_5") (pintype "power_in"))
    )
    (net (code "2") (name "+12V") (class "Default")
      (node (ref "C3") (pin "2") (pinfunction "2_2") (pintype "passive"))
      (node (ref "C67") (pin "2") (pinfunction "2_2") (pintype "passive"))
      (node (ref "DC/DC-3V3") (pin "1/VIN") (pinfunction "1/VIN_1/VIN") (pintype "bidirectional"))
      (node (ref "J_-VLOAD") (pin "11") (pinfunction "11_11") (pintype "passive"))
      (node (ref "QP2") (pin "P$3") (pinfunction "S_P$3") (pintype "bidirectional"))
      (node (ref "QP3") (pin "P$3") (pinfunction "S_P$3") (pintype "bidirectional"))
      (node (ref "QP4") (pin "P$3") (pinfunction "S_P$3") (pintype "bidirectional"))
      (node (ref "QP5") (pin "P$3") (pinfunction "S_P$3") (pintype "bidirectional"))
      (node (ref "QP6") (pin "P$3") (pinfunction "S_P$3") (pintype "bidirectional"))
      (node (ref "RGS2") (pin "1") (pinfunction "1_1") (pintype "passive"))
      (node (ref "RGS6") (pin "1") (pinfunction "1_1") (pintype "passive"))
      (node (ref "RLD3") (pin "1") (pinfunction "1_1") (pintype "passive"))
      (node (ref "TP-12V2") (pin "P1") (pinfunction "P$1_P1") (pintype "bidirectional"))
    )
    (net (code "3") (name "+12VDRV") (class "Default")
      (node (ref "J_-VLOAD") (pin "12") (pinfunction "12_12") (pintype "passive"))
      (node (ref "QN4") (pin "P$2") (pinfunction "G_P$2") (pintype "bidirectional"))
      (node (ref "QP2") (pin "P$1") (pinfunction "D_P$1") (pintype "bidirectional"))
      (node (ref "QP5") (pin "P$1") (pinfunction "D_P$1") (pintype "bidirectional"))
      (node (ref "QP6") (pin "P$1") (pinfunction "D_P$1") (pintype "bidirectional"))
      (node (ref "RGS4") (pin "1") (pinfunction "1_1") (pintype "passive"))
      (node (ref "R_ILIM2") (pin "1") (pinfunction "1_1") (pintype "passive"))
      (node (ref "R_ILIM3") (pin "1") (pinfunction "1_1") (pintype "passive"))
      (node (ref "TP_12VDRV") (pin "P1") (pinfunction "P$1_P1") (pintype "bidirectional"))
    )
    (net (code "4") (name "-VLOAD") (class "Default")
      (node (ref "D1") (pin "A") (pinfunction "A_A") (pintype "passive"))
      (node (ref "J_-VLOAD") (pin "1") (pinfunction "1_1") (pintype "passive"))
      (node (ref "J_-VLOAD") (pin "2") (pinfunction "2_2") (pintype "passive"))
      (node (ref "J_-VLOAD") (pin "3") (pinfunction "3_3") (pintype "passive"))
      (node (ref "J_-VLOAD") (pin "4") (pinfunction "4_4") (pintype "passive"))
      (node (ref "J_-VLOAD") (pin "5") (pinfunction "5_5") (pintype "passive"))
      (node (ref "J_-VLOAD") (pin "6") (pinfunction "6_6") (pintype "passive"))
      (node (ref "J_-VLOAD") (pin "7") (pinfunction "7_7") (pintype "passive"))
      (node (ref "J_-VLOAD") (pin "8") (pinfunction "8_8") (pintype "passive"))
      (node (ref "QN_SSR1") (pin "3") (pinfunction "S_3") (pintype "bidirectional"))
      (node (ref "QN_SSR3") (pin "3") (pinfunction "S_3") (pintype "bidirectional"))
      (node (ref "TP_-VLOAD") (pin "P1") (pinfunction "P$1_P1") (pintype "bidirectional"))
    )
    (net (code "5") (name "-VLOAD_SW") (class "Default")
      (node (ref "CF2") (pin "1") (pinfunction "1_1") (pintype "passive"))
      (node (ref "J_BATT/GND") (pin "9") (pinfunction "9_9") (pintype "passive"))
      (node (ref "QN_SSR2") (pin "3") (pinfunction "S_3") (pintype "bidirectional"))
      (node (ref "QN_SSR4") (pin "3") (pinfunction "S_3") (pintype "bidirectional"))
      (node (ref "RF1") (pin "2") (pinfunction "2_2") (pintype "passive"))
      (node (ref "RSHUNT1") (pin "2") (pinfunction "2_2") (pintype "passive"))
      (node (ref "RSHUNT2") (pin "2") (pinfunction "2_2") (pintype "passive"))
      (node (ref "RSHUNT3") (pin "2") (pinfunction "2_2") (pintype "passive"))
      (node (ref "RSHUNT4") (pin "2") (pinfunction "2_2") (pintype "passive"))
      (node (ref "TP_-VLD_SW2") (pin "P1") (pinfunction "P$1_P1") (pintype "bidirectional"))
    )
    (net (code "6") (name "AMP_OUT") (class "Default")
      (node (ref "AMP_OUT") (pin "P1") (pinfunction "P$1_P1") (pintype "bidirectional"))
      (node (ref "RF2") (pin "1") (pinfunction "1_1") (pintype "passive"))
      (node (ref "RPU3") (pin "1") (pinfunction "1_1") (pintype "passive"))
      (node (ref "U2") (pin "3") (pinfunction "IN-_3") (pintype "input"))
    )
    (net (code "7") (name "COMPARATOR_OUT") (class "Default")
      (node (ref "QP1") (pin "P$2") (pinfunction "G_P$2") (pintype "bidirectional"))
      (node (ref "RPU2") (pin "2") (pinfunction "2_2") (pintype "passive"))
      (node (ref "TP_COMP_OUT") (pin "P1") (pinfunction "P$1_P1") (pintype "bidirectional"))
      (node (ref "U2") (pin "4") (pinfunction "OUT_4") (pintype "output"))
    )
    (net (code "8") (name "EFUSE_TRIP") (class "Default")
      (node (ref "J_BATT/GND") (pin "10") (pinfunction "10_10") (pintype "passive"))
      (node (ref "QN1") (pin "P$2") (pinfunction "G_P$2") (pintype "bidirectional"))
      (node (ref "QN10") (pin "P$2") (pinfunction "G_P$2") (pintype "bidirectional"))
      (node (ref "QN2") (pin "P$2") (pinfunction "G_P$2") (pintype "bidirectional"))
      (node (ref "QN3") (pin "P$2") (pinfunction "G_P$2") (pintype "bidirectional"))
      (node (ref "QP1") (pin "P$1") (pinfunction "D_P$1") (pintype "bidirectional"))
      (node (ref "RGS1") (pin "1") (pinfunction "1_1") (pintype "passive"))
      (node (ref "RGS3") (pin "1") (pinfunction "1_1") (pintype "passive"))
      (node (ref "RGS5") (pin "1") (pinfunction "1_1") (pintype "passive"))
      (node (ref "RGS9") (pin "1") (pinfunction "1_1") (pintype "passive"))
      (node (ref "RLD2") (pin "1") (pinfunction "1_1") (pintype "passive"))
      (node (ref "RPD5") (pin "1") (pinfunction "1_1") (pintype "passive"))
      (node (ref "TP_EFUSE_TRIP") (pin "P1") (pinfunction "P$1_P1") (pintype "bidirectional"))
    )
    (net (code "9") (name "GND") (class "Default")
      (node (ref "C3") (pin "1") (pinfunction "1_1") (pintype "passive"))
      (node (ref "C5") (pin "2") (pinfunction "2_2") (pintype "passive"))
      (node (ref "C67") (pin "1") (pinfunction "1_1") (pintype "passive"))
      (node (ref "C9") (pin "1") (pinfunction "1_1") (pintype "passive"))
      (node (ref "CF1") (pin "2") (pinfunction "2_2") (pintype "passive"))
      (node (ref "CF2") (pin "2") (pinfunction "2_2") (pintype "passive"))
      (node (ref "CVREF1") (pin "2") (pinfunction "2_2") (pintype "passive"))
      (node (ref "DC/DC-3V3") (pin "2/GND") (pinfunction "2/GND_2/GND") (pintype "bidirectional"))
      (node (ref "GND2") (pin "P1") (pinfunction "P$1_P1") (pintype "bidirectional"))
      (node (ref "GND3") (pin "P1") (pinfunction "P$1_P1") (pintype "bidirectional"))
      (node (ref "GND4") (pin "P1") (pinfunction "P$1_P1") (pintype "bidirectional"))
      (node (ref "J_-VLOAD") (pin "9") (pinfunction "9_9") (pintype "passive"))
      (node (ref "J_BATT/GND") (pin "1") (pinfunction "1_1") (pintype "passive"))
      (node (ref "J_BATT/GND") (pin "2") (pinfunction "2_2") (pintype "passive"))
      (node (ref "J_BATT/GND") (pin "3") (pinfunction "3_3") (pintype "passive"))
      (node (ref "J_BATT/GND") (pin "4") (pinfunction "4_4") (pintype "passive"))
      (node (ref "J_BATT/GND") (pin "5") (pinfunction "5_5") (pintype "passive"))
      (node (ref "J_BATT/GND") (pin "6") (pinfunction "6_6") (pintype "passive"))
      (node (ref "J_BATT/GND") (pin "7") (pinfunction "7_7") (pintype "passive"))
      (node (ref "J_BATT/GND") (pin "8") (pinfunction "8_8") (pintype "passive"))
      (node (ref "LED_12V") (pin "C") (pinfunction "C_C") (pintype "passive"))
      (node (ref "LED_3V3") (pin "C") (pinfunction "C_C") (pintype "passive"))
      (node (ref "L_EFUSE_TRIP") (pin "C") (pinfunction "C_C") (pintype "passive"))
      (node (ref "QN1") (pin "P$3") (pinfunction "S_P$3") (pintype "bidirectional"))
      (node (ref "QN11") (pin "P$3") (pinfunction "S_P$3") (pintype "bidirectional"))
      (node (ref "QN2") (pin "P$3") (pinfunction "S_P$3") (pintype "bidirectional"))
      (node (ref "QN3") (pin "P$3") (pinfunction "S_P$3") (pintype "bidirectional"))
      (node (ref "QN4") (pin "P$3") (pinfunction "S_P$3") (pintype "bidirectional"))
      (node (ref "RGS1") (pin "2") (pinfunction "2_2") (pintype "passive"))
      (node (ref "RGS10") (pin "2") (pinfunction "2_2") (pintype "passive"))
      (node (ref "RGS4") (pin "2") (pinfunction "2_2") (pintype "passive"))
      (node (ref "RGS5") (pin "2") (pinfunction "2_2") (pintype "passive"))
      (node (ref "RGS7") (pin "2") (pinfunction "2_2") (pintype "passive"))
      (node (ref "RGS9") (pin "2") (pinfunction "2_2") (pintype "passive"))
      (node (ref "RPD5") (pin "2") (pinfunction "2_2") (pintype "passive"))
      (node (ref "RSHUNT1") (pin "1") (pinfunction "1_1") (pintype "passive"))
      (node (ref "RSHUNT2") (pin "1") (pinfunction "1_1") (pintype "passive"))
      (node (ref "RSHUNT3") (pin "1") (pinfunction "1_1") (pintype "passive"))
      (node (ref "RSHUNT4") (pin "1") (pinfunction "1_1") (pintype "passive"))
      (node (ref "SJ1") (pin "2") (pinfunction "2_2") (pintype "passive"))
      (node (ref "SW_EFUSE_RST") (pin "1") (pinfunction "1_1") (pintype "passive"))
      (node (ref "SW_EFUSE_RST1") (pin "1") (pinfunction "1_1") (pintype "passive"))
      (node (ref "U2") (pin "2") (pinfunction "V-_2") (pintype "power_in"))
    )
    (net (code "10") (name "Net-(CF1-Pad1)") (class "Default")
      (node (ref "CF1") (pin "1") (pinfunction "1_1") (pintype "passive"))
      (node (ref "RF1") (pin "1") (pinfunction "1_1") (pintype "passive"))
      (node (ref "RF2") (pin "2") (pinfunction "2_2") (pintype "passive"))
    )
    (net (code "11") (name "Net-(DZ_15V1-C)") (class "Default")
      (node (ref "D1") (pin "C") (pinfunction "C_C") (pintype "passive"))
      (node (ref "DZ_15V1") (pin "1") (pinfunction "C_1") (pintype "passive"))
    )
    (net (code "12") (name "Net-(EFUSE_LIM-Pad1)") (class "Default")
      (node (ref "EFUSE_LIM") (pin "1") (pinfunction "1_1") (pintype "passive"))
      (node (ref "SJ1") (pin "1") (pinfunction "1_1") (pintype "passive"))
    )
    (net (code "13") (name "Net-(EFUSE_LIM-Pad2)") (class "Default")
      (node (ref "EFUSE_LIM") (pin "2") (pinfunction "2_2") (pintype "passive"))
      (node (ref "RVRF2") (pin "2") (pinfunction "2_2") (pintype "passive"))
    )
    (net (code "14") (name "Net-(EFUSE_LIM-Pad3)") (class "Default")
      (node (ref "EFUSE_LIM") (pin "3") (pinfunction "3_3") (pintype "passive"))
      (node (ref "SJ1") (pin "3") (pinfunction "3_3") (pintype "passive"))
    )
    (net (code "15") (name "Net-(LED_3V3-PadA)") (class "Default")
      (node (ref "LED_3V3") (pin "A") (pinfunction "A_A") (pintype "passive"))
      (node (ref "RLD1") (pin "2") (pinfunction "2_2") (pintype "passive"))
    )
    (net (code "16") (name "Net-(LED_12V-PadA)") (class "Default")
      (node (ref "LED_12V") (pin "A") (pinfunction "A_A") (pintype "passive"))
      (node (ref "RLD3") (pin "2") (pinfunction "2_2") (pintype "passive"))
    )
    (net (code "17") (name "Net-(L_EFUSE_TRIP-PadA)") (class "Default")
      (node (ref "L_EFUSE_TRIP") (pin "A") (pinfunction "A_A") (pintype "passive"))
      (node (ref "RLD2") (pin "2") (pinfunction "2_2") (pintype "passive"))
    )
    (net (code "18") (name "Net-(QN1-D)") (class "Default")
      (node (ref "QN1") (pin "P$1") (pinfunction "D_P$1") (pintype "bidirectional"))
      (node (ref "R_ILIM2") (pin "2") (pinfunction "2_2") (pintype "passive"))
      (node (ref "R_ILIM3") (pin "2") (pinfunction "2_2") (pintype "passive"))
    )
    (net (code "19") (name "Net-(QN2-D)") (class "Default")
      (node (ref "QN2") (pin "P$1") (pinfunction "D_P$1") (pintype "bidirectional"))
      (node (ref "QP3") (pin "P$2") (pinfunction "G_P$2") (pintype "bidirectional"))
      (node (ref "RGS2") (pin "2") (pinfunction "2_2") (pintype "passive"))
    )
    (net (code "20") (name "Net-(QN3-D)") (class "Default")
      (node (ref "QN3") (pin "P$1") (pinfunction "D_P$1") (pintype "bidirectional"))
      (node (ref "R_ILIM1") (pin "2") (pinfunction "2_2") (pintype "passive"))
      (node (ref "R_ILIM4") (pin "2") (pinfunction "2_2") (pintype "passive"))
    )
    (net (code "21") (name "Net-(QN4-D)") (class "Default")
      (node (ref "QN4") (pin "P$1") (pinfunction "D_P$1") (pintype "bidirectional"))
      (node (ref "QP4") (pin "P$2") (pinfunction "G_P$2") (pintype "bidirectional"))
      (node (ref "RGS6") (pin "2") (pinfunction "2_2") (pintype "passive"))
    )
    (net (code "22") (name "Net-(QN10-D)") (class "Default")
      (node (ref "QN10") (pin "P$1") (pinfunction "D_P$1") (pintype "bidirectional"))
      (node (ref "RF3") (pin "2") (pinfunction "2_2") (pintype "passive"))
    )
    (net (code "23") (name "Net-(QN10-S)") (class "Default")
      (node (ref "QN10") (pin "P$3") (pinfunction "S_P$3") (pintype "bidirectional"))
      (node (ref "QN11") (pin "P$1") (pinfunction "D_P$1") (pintype "bidirectional"))
      (node (ref "RGS3") (pin "2") (pinfunction "2_2") (pintype "passive"))
    )
    (net (code "24") (name "Net-(QN_SSR1-D)") (class "Default")
      (node (ref "QN_SSR1") (pin "2") (pinfunction "D_2") (pintype "bidirectional"))
      (node (ref "QN_SSR2") (pin "2") (pinfunction "D_2") (pintype "bidirectional"))
      (node (ref "QN_SSR3") (pin "2") (pinfunction "D_2") (pintype "bidirectional"))
      (node (ref "QN_SSR4") (pin "2") (pinfunction "D_2") (pintype "bidirectional"))
    )
    (net (code "25") (name "Net-(QN_SSR1-G)") (class "Default")
      (node (ref "QN_SSR1") (pin "1") (pinfunction "G_1") (pintype "bidirectional"))
      (node (ref "RG2") (pin "1") (pinfunction "1_1") (pintype "passive"))
    )
    (net (code "26") (name "Net-(QN_SSR2-G)") (class "Default")
      (node (ref "QN_SSR2") (pin "1") (pinfunction "G_1") (pintype "bidirectional"))
      (node (ref "RG3") (pin "1") (pinfunction "1_1") (pintype "passive"))
    )
    (net (code "27") (name "Net-(QN_SSR3-G)") (class "Default")
      (node (ref "QN_SSR3") (pin "1") (pinfunction "G_1") (pintype "bidirectional"))
      (node (ref "RG1") (pin "1") (pinfunction "1_1") (pintype "passive"))
    )
    (net (code "28") (name "Net-(QN_SSR4-G)") (class "Default")
      (node (ref "QN_SSR4") (pin "1") (pinfunction "G_1") (pintype "bidirectional"))
      (node (ref "RG4") (pin "1") (pinfunction "1_1") (pintype "passive"))
    )
    (net (code "29") (name "Net-(QP2-G)") (class "Default")
      (node (ref "QP2") (pin "P$2") (pinfunction "G_P$2") (pintype "bidirectional"))
      (node (ref "QP3") (pin "P$1") (pinfunction "D_P$1") (pintype "bidirectional"))
      (node (ref "QP5") (pin "P$2") (pinfunction "G_P$2") (pintype "bidirectional"))
      (node (ref "QP6") (pin "P$2") (pinfunction "G_P$2") (pintype "bidirectional"))
      (node (ref "RGS10") (pin "1") (pinfunction "1_1") (pintype "passive"))
    )
    (net (code "30") (name "Net-(R1-Pad2)") (class "Default")
      (node (ref "R1") (pin "2") (pinfunction "2_2") (pintype "passive"))
      (node (ref "SW_EFUSE_RST") (pin "2") (pinfunction "2_2") (pintype "passive"))
      (node (ref "SW_EFUSE_RST1") (pin "2") (pinfunction "2_2") (pintype "passive"))
    )
    (net (code "31") (name "SSR_G") (class "Default")
      (node (ref "DZ_15V1") (pin "2") (pinfunction "A_2") (pintype "passive"))
      (node (ref "QP4") (pin "P$1") (pinfunction "D_P$1") (pintype "bidirectional"))
      (node (ref "RG1") (pin "2") (pinfunction "2_2") (pintype "passive"))
      (node (ref "RG2") (pin "2") (pinfunction "2_2") (pintype "passive"))
      (node (ref "RG3") (pin "2") (pinfunction "2_2") (pintype "passive"))
      (node (ref "RG4") (pin "2") (pinfunction "2_2") (pintype "passive"))
      (node (ref "RGS7") (pin "1") (pinfunction "1_1") (pintype "passive"))
      (node (ref "R_ILIM1") (pin "1") (pinfunction "1_1") (pintype "passive"))
      (node (ref "R_ILIM4") (pin "1") (pinfunction "1_1") (pintype "passive"))
      (node (ref "TP-SSR_G") (pin "P1") (pinfunction "P$1_P1") (pintype "bidirectional"))
    )
    (net (code "32") (name "VREF") (class "Default")
      (node (ref "CVREF1") (pin "1") (pinfunction "1_1") (pintype "passive"))
      (node (ref "J_BATT/GND") (pin "11") (pinfunction "11_11") (pintype "passive"))
      (node (ref "RF3") (pin "1") (pinfunction "1_1") (pintype "passive"))
      (node (ref "RVRF1") (pin "2") (pinfunction "2_2") (pintype "passive"))
      (node (ref "RVRF2") (pin "1") (pinfunction "1_1") (pintype "passive"))
      (node (ref "TP_VREF") (pin "P1") (pinfunction "P$1_P1") (pintype "bidirectional"))
      (node (ref "U2") (pin "1") (pinfunction "IN+_1") (pintype "input"))
    )
    (net (code "33") (name "unconnected-(MS1-Pad1)") (class "Default")
      (node (ref "MS1") (pin "1") (pinfunction "1_1") (pintype "passive"))
    )
    (net (code "34") (name "unconnected-(MS2-Pad1)") (class "Default")
      (node (ref "MS2") (pin "1") (pinfunction "1_1") (pintype "passive"))
    )
    (net (code "35") (name "~{EFUSE_RST}") (class "Default")
      (node (ref "J_BATT/GND") (pin "12") (pinfunction "12_12") (pintype "passive"))
      (node (ref "QN11") (pin "P$2") (pinfunction "G_P$2") (pintype "bidirectional"))
      (node (ref "R1") (pin "1") (pinfunction "1_1") (pintype "passive"))
      (node (ref "RGD1") (pin "2") (pinfunction "2_2") (pintype "passive"))
      (node (ref "TP_!EFUSE_RST") (pin "P1") (pinfunction "P$1_P1") (pintype "bidirectional"))
    )
  )
)
